# Quad_ESC.net
KiCad netlist of a schematic drawn in EAGLE
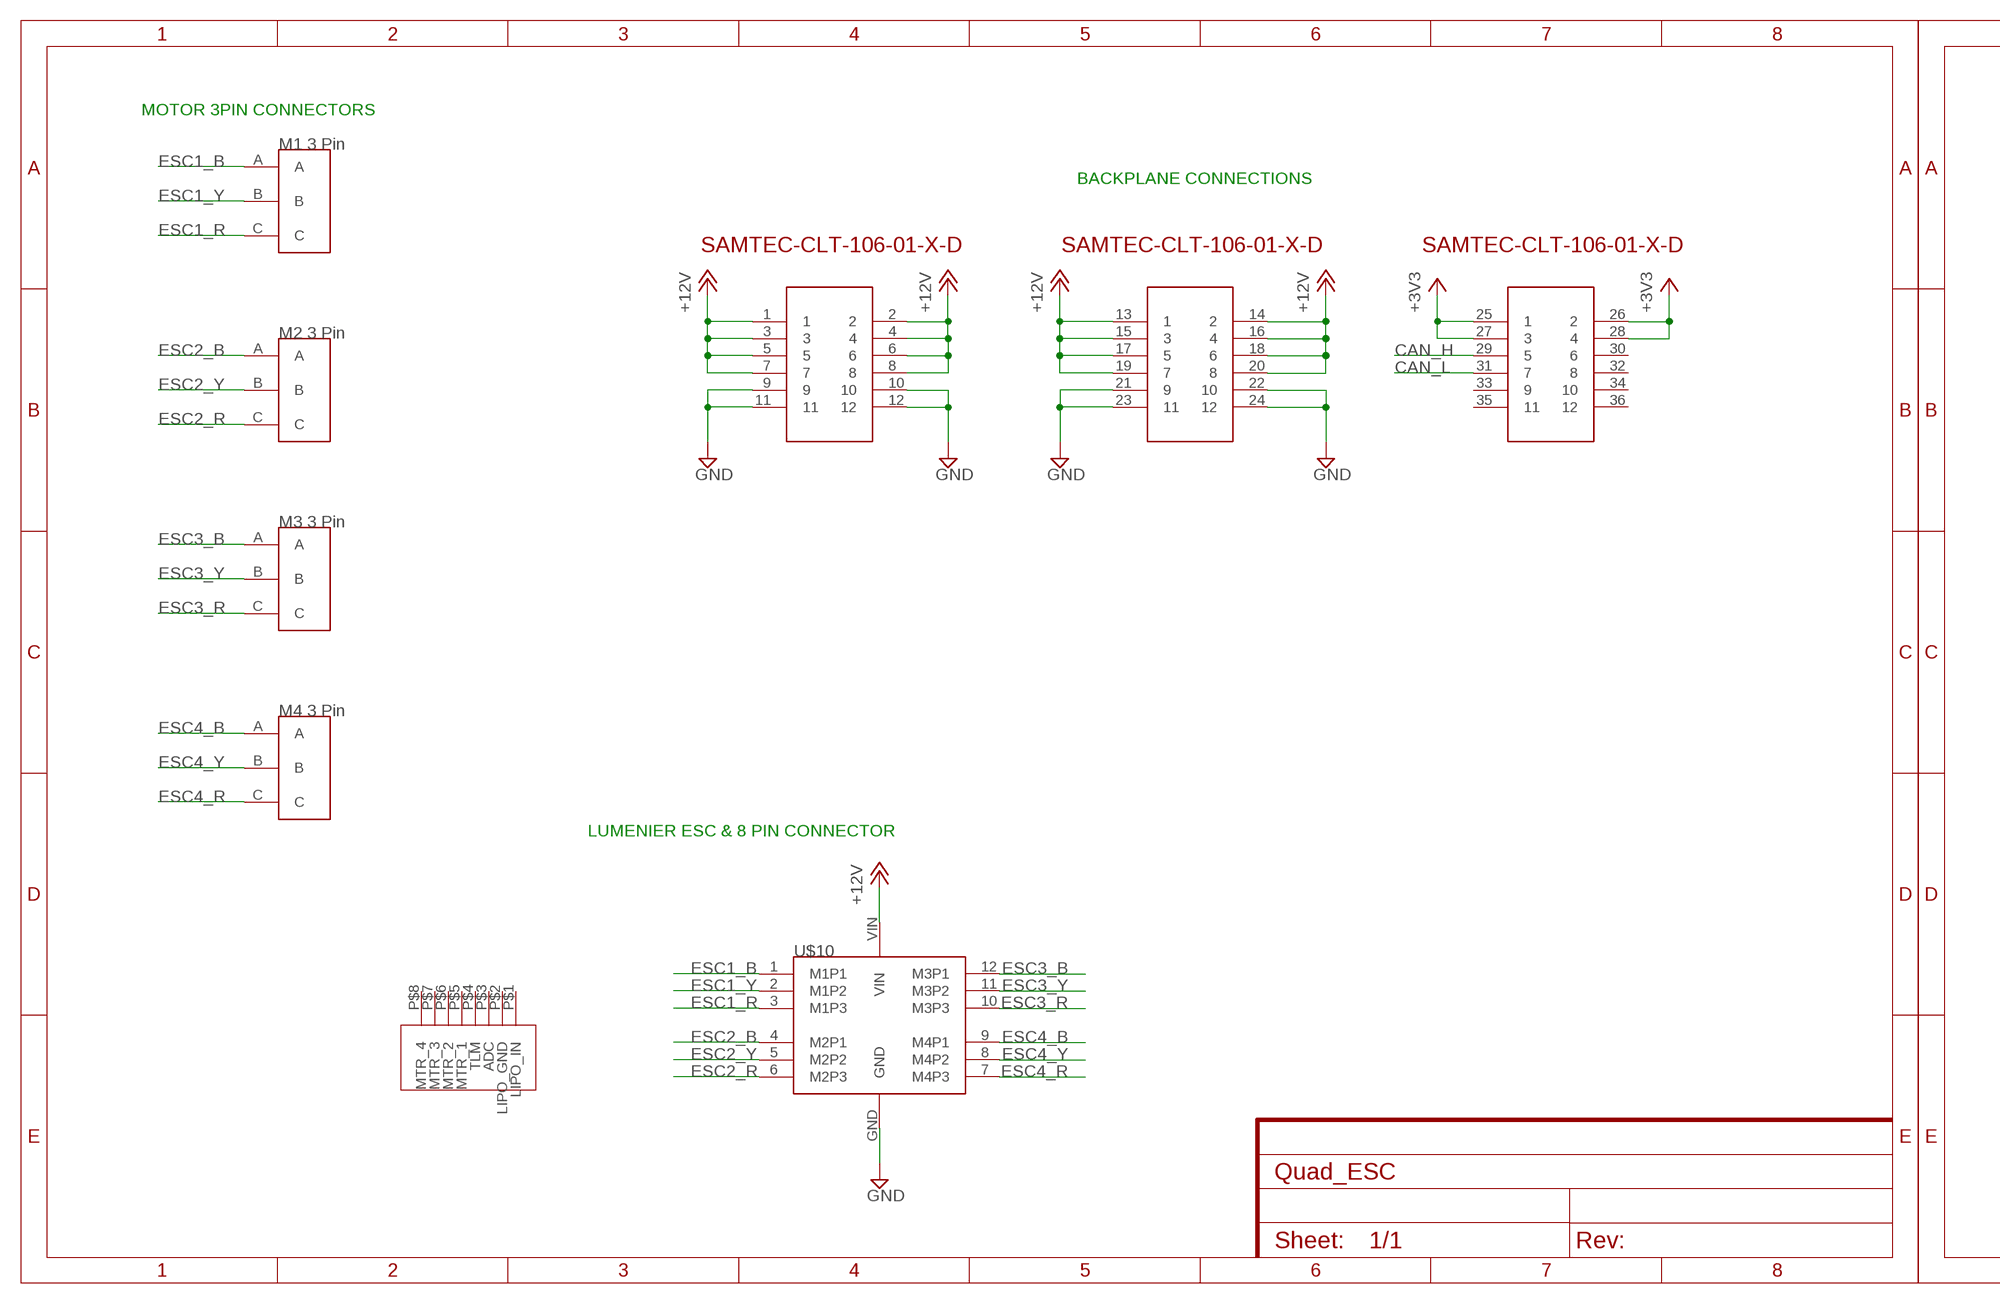
[diagram p0: schematic, sheet 1, part 1 of 2]
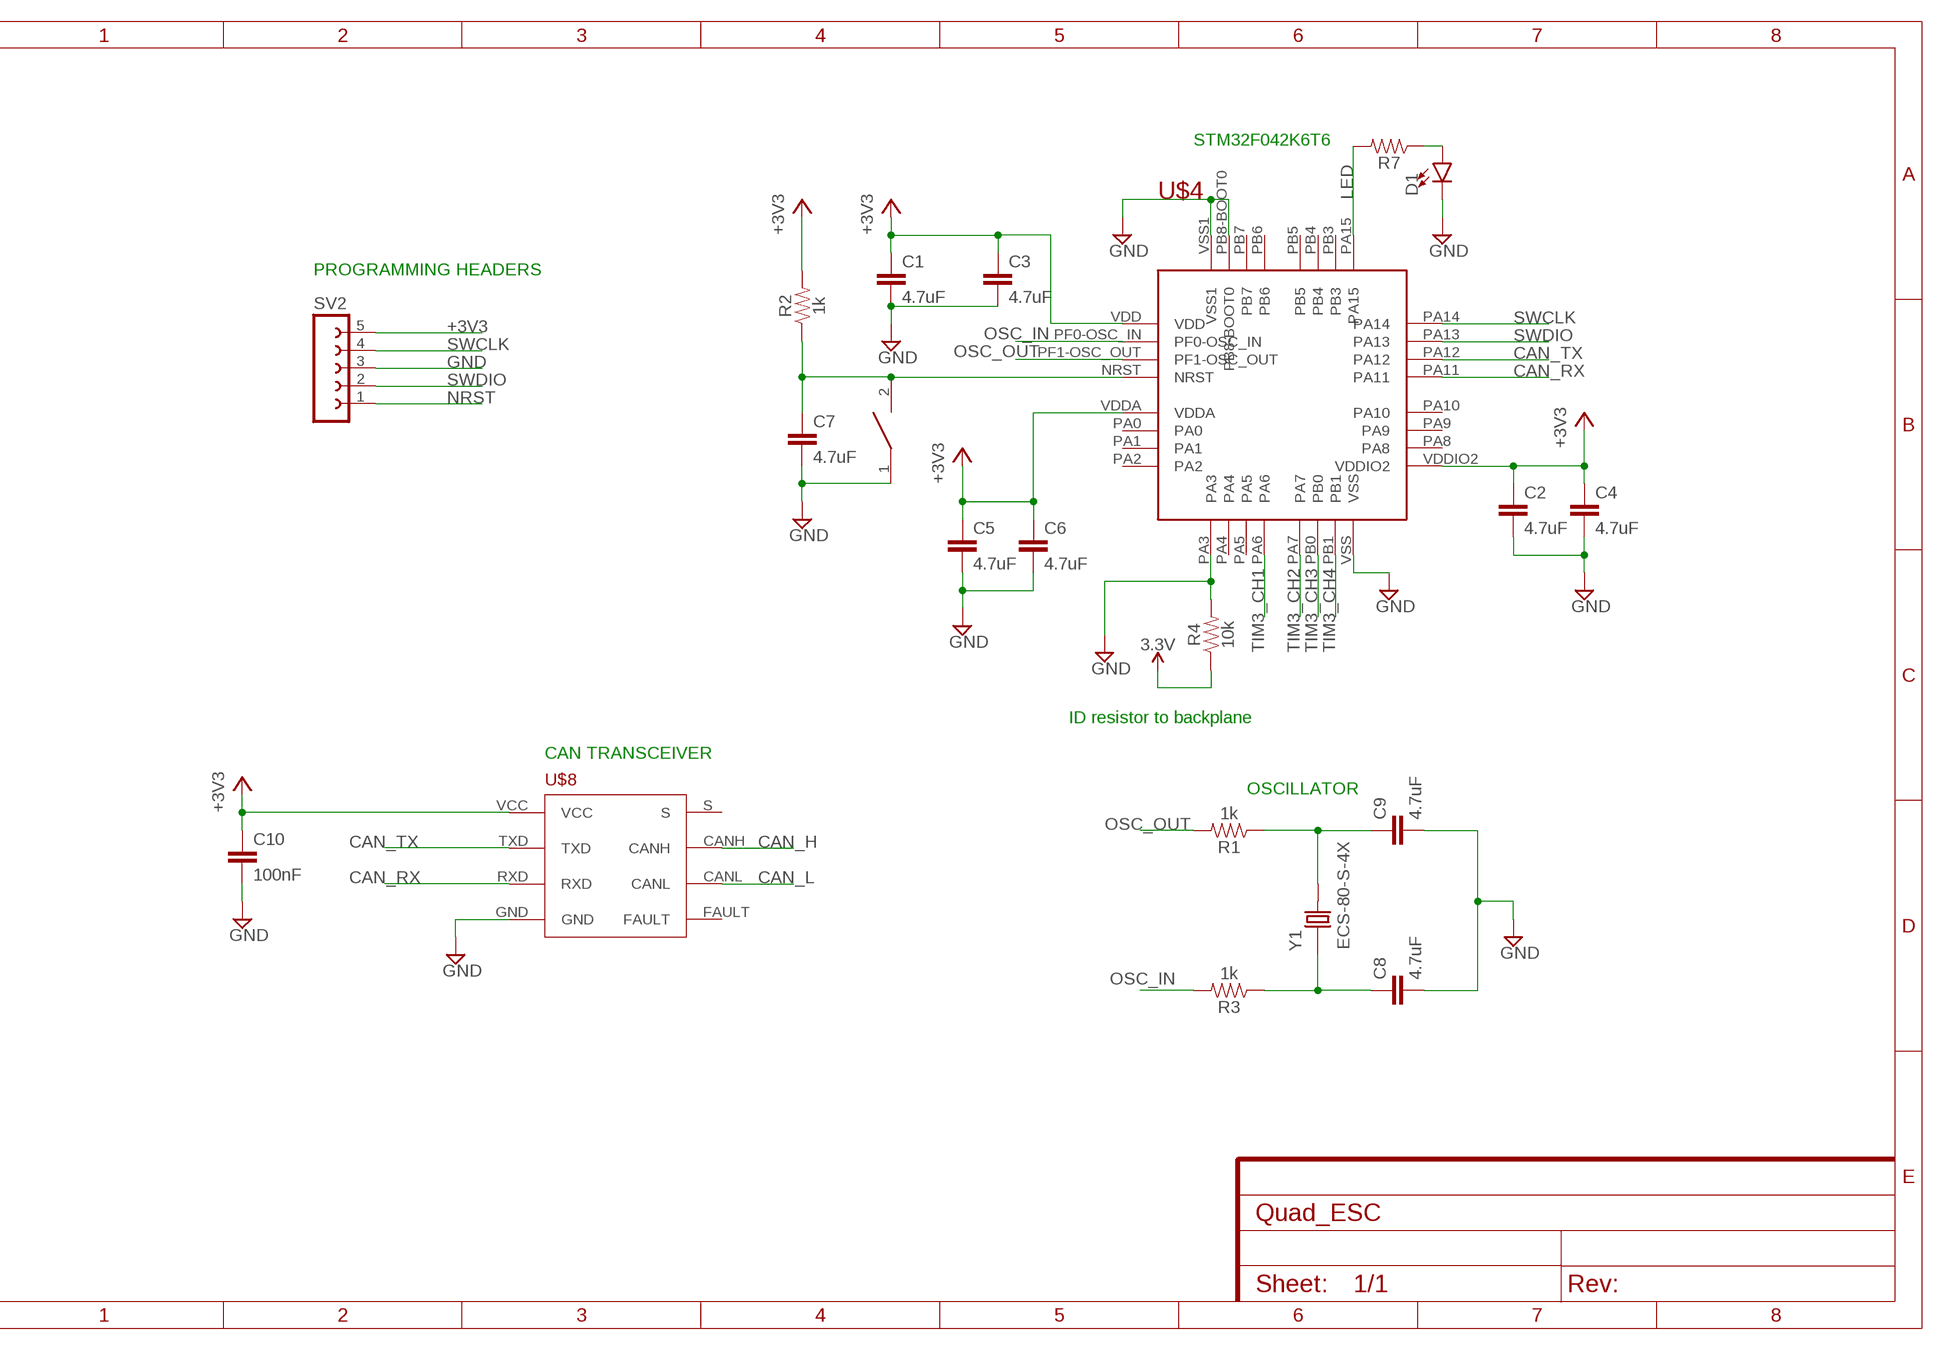
[diagram p1: schematic, sheet 1, part 2 of 2]

(export (version "E")
  (design (tool "Eeschema 10.0.6"))
  (components
    (comp (ref "C1")
      (value "4.7uF")
      (footprint "eagle-import:0603")
      (libsource (lib "eagle-import") (part "4.7UF0603"))
    )
    (comp (ref "C2")
      (value "4.7uF")
      (footprint "eagle-import:0603")
      (libsource (lib "eagle-import") (part "4.7UF0603"))
    )
    (comp (ref "C3")
      (value "4.7uF")
      (footprint "eagle-import:0603")
      (libsource (lib "eagle-import") (part "4.7UF0603"))
    )
    (comp (ref "C4")
      (value "4.7uF")
      (footprint "eagle-import:0603")
      (libsource (lib "eagle-import") (part "4.7UF0603"))
    )
    (comp (ref "C5")
      (value "4.7uF")
      (footprint "eagle-import:0603")
      (libsource (lib "eagle-import") (part "4.7UF0603"))
    )
    (comp (ref "C6")
      (value "4.7uF")
      (footprint "eagle-import:0603")
      (libsource (lib "eagle-import") (part "4.7UF0603"))
    )
    (comp (ref "C7")
      (value "4.7uF")
      (footprint "eagle-import:0603")
      (libsource (lib "eagle-import") (part "4.7UF0603"))
    )
    (comp (ref "C8")
      (value "4.7uF")
      (footprint "eagle-import:0603")
      (libsource (lib "eagle-import") (part "4.7UF0603"))
    )
    (comp (ref "C9")
      (value "4.7uF")
      (footprint "eagle-import:0603")
      (libsource (lib "eagle-import") (part "4.7UF0603"))
    )
    (comp (ref "C10")
      (value "100nF")
      (footprint "eagle-import:0603")
      (libsource (lib "eagle-import") (part "4.7UF0603"))
    )
    (comp (ref "D1")
      (value "LED0603")
      (footprint "eagle-import:LED-0603")
      (libsource (lib "eagle-import") (part "LED0603"))
    )
    (comp (ref "R1")
      (value "1k")
      (footprint "eagle-import:0603")
      (libsource (lib "eagle-import") (part "1KOHM-0603-1/10W-1%"))
    )
    (comp (ref "R2")
      (value "1k")
      (footprint "eagle-import:0603")
      (libsource (lib "eagle-import") (part "1KOHM-0603-1/10W-1%"))
    )
    (comp (ref "R3")
      (value "1k")
      (footprint "eagle-import:0603")
      (libsource (lib "eagle-import") (part "1KOHM-0603-1/10W-1%"))
    )
    (comp (ref "R4")
      (value "10k")
      (footprint "eagle-import:0603")
      (libsource (lib "eagle-import") (part "10KOHM-0603-1/10W-1%"))
    )
    (comp (ref "R7")
      (value "RESISTOR0603")
      (footprint "eagle-import:0603")
      (libsource (lib "eagle-import") (part "RESISTOR0603"))
    )
    (comp (ref "RESET")
      (value "SWITCH")
      (footprint "eagle-import:SW_2512")
      (libsource (lib "eagle-import") (part "SWITCH"))
    )
    (comp (ref "SV2")
      (value "FE05-1")
      (footprint "eagle-import:FE05-1")
      (libsource (lib "eagle-import") (part "FE05-1"))
    )
    (comp (ref "U$1")
      (value "3PINCONNECTOR")
      (footprint "eagle-import:3PINCONNECTOR")
      (libsource (lib "eagle-import") (part "3PINCONNECTOR"))
    )
    (comp (ref "U$2")
      (value "8PIN_CONNECTOR")
      (footprint "eagle-import:8PI_CONNECTOR")
      (libsource (lib "eagle-import") (part "8PIN_CONNECTOR"))
    )
    (comp (ref "U$3")
      (value "BACKPLANE_CONNECTORS")
      (footprint "eagle-import:BACKPLANE_CONNECTORS")
      (libsource (lib "eagle-import") (part "BACKPLANE_CONNECTORS"))
    )
    (comp (ref "U$4")
      (value "STM32F042K6T6")
      (footprint "eagle-import:STM32F042K6T6")
      (libsource (lib "eagle-import") (part "STM32F042K6T6"))
    )
    (comp (ref "U$5")
      (value "3PINCONNECTOR")
      (footprint "eagle-import:3PINCONNECTOR")
      (libsource (lib "eagle-import") (part "3PINCONNECTOR"))
    )
    (comp (ref "U$6")
      (value "3PINCONNECTOR")
      (footprint "eagle-import:3PINCONNECTOR")
      (libsource (lib "eagle-import") (part "3PINCONNECTOR"))
    )
    (comp (ref "U$7")
      (value "3PINCONNECTOR")
      (footprint "eagle-import:3PINCONNECTOR")
      (libsource (lib "eagle-import") (part "3PINCONNECTOR"))
    )
    (comp (ref "U$8")
      (value "TCAN337D")
      (footprint "eagle-import:TCAN337D")
      (libsource (lib "eagle-import") (part "TCAN337D"))
    )
    (comp (ref "U$10")
      (value "LUMENIER_QUAD")
      (footprint "eagle-import:LUMENIER_QUAD")
      (libsource (lib "eagle-import") (part "LUMENIER_QUAD"))
    )
    (comp (ref "Y1")
      (value "ECS-80-S-4X")
      (footprint "eagle-import:XTAL_ECS-80-S-4X")
      (fields (field (name "DIGI-KEY_PART_NUMBER") "X1057-ND") (field (name "MF") "ECS International"))
      (libsource (lib "eagle-import") (part "ECS-80-S-4X"))
    )
  )
  (nets
    (net (code "1") (name "+3V3") (class "Default")
      (node (ref "C1") (pin "1") (pinfunction "1_1") (pintype "passive"))
      (node (ref "C10") (pin "1") (pinfunction "1_1") (pintype "passive"))
      (node (ref "C2") (pin "1") (pinfunction "1_1") (pintype "passive"))
      (node (ref "C3") (pin "1") (pinfunction "1_1") (pintype "passive"))
      (node (ref "C4") (pin "1") (pinfunction "1_1") (pintype "passive"))
      (node (ref "C5") (pin "1") (pinfunction "1_1") (pintype "passive"))
      (node (ref "C6") (pin "1") (pinfunction "1_1") (pintype "passive"))
      (node (ref "R2") (pin "2") (pinfunction "2_2") (pintype "passive"))
      (node (ref "SV2") (pin "5") (pinfunction "5_5") (pintype "passive"))
      (node (ref "U$3") (pin "25") (pinfunction "1_25") (pintype "passive"))
      (node (ref "U$3") (pin "26") (pinfunction "2_26") (pintype "passive"))
      (node (ref "U$3") (pin "27") (pinfunction "3_27") (pintype "passive"))
      (node (ref "U$3") (pin "28") (pinfunction "4_28") (pintype "passive"))
      (node (ref "U$4") (pin "VDD") (pinfunction "VDD_VDD") (pintype "bidirectional"))
      (node (ref "U$4") (pin "VDDA") (pinfunction "VDDA_VDDA") (pintype "bidirectional"))
      (node (ref "U$4") (pin "VDDIO2") (pinfunction "VDDIO2_VDDIO2") (pintype "bidirectional"))
      (node (ref "U$8") (pin "VCC") (pinfunction "VCC_VCC") (pintype "bidirectional"))
    )
    (net (code "2") (name "+12V") (class "Default")
      (node (ref "U$10") (pin "VIN") (pinfunction "VIN_VIN") (pintype "bidirectional"))
      (node (ref "U$3") (pin "1") (pinfunction "1_1") (pintype "passive"))
      (node (ref "U$3") (pin "13") (pinfunction "1_13") (pintype "passive"))
      (node (ref "U$3") (pin "14") (pinfunction "2_14") (pintype "passive"))
      (node (ref "U$3") (pin "15") (pinfunction "3_15") (pintype "passive"))
      (node (ref "U$3") (pin "16") (pinfunction "4_16") (pintype "passive"))
      (node (ref "U$3") (pin "17") (pinfunction "5_17") (pintype "passive"))
      (node (ref "U$3") (pin "18") (pinfunction "6_18") (pintype "passive"))
      (node (ref "U$3") (pin "19") (pinfunction "7_19") (pintype "passive"))
      (node (ref "U$3") (pin "2") (pinfunction "2_2") (pintype "passive"))
      (node (ref "U$3") (pin "20") (pinfunction "8_20") (pintype "passive"))
      (node (ref "U$3") (pin "3") (pinfunction "3_3") (pintype "passive"))
      (node (ref "U$3") (pin "4") (pinfunction "4_4") (pintype "passive"))
      (node (ref "U$3") (pin "5") (pinfunction "5_5") (pintype "passive"))
      (node (ref "U$3") (pin "6") (pinfunction "6_6") (pintype "passive"))
      (node (ref "U$3") (pin "7") (pinfunction "7_7") (pintype "passive"))
      (node (ref "U$3") (pin "8") (pinfunction "8_8") (pintype "passive"))
    )
    (net (code "3") (name "/CAN_H") (class "Default")
      (node (ref "U$3") (pin "29") (pinfunction "5_29") (pintype "passive"))
      (node (ref "U$8") (pin "CANH") (pinfunction "CANH_CANH") (pintype "bidirectional"))
    )
    (net (code "4") (name "/CAN_L") (class "Default")
      (node (ref "U$3") (pin "31") (pinfunction "7_31") (pintype "passive"))
      (node (ref "U$8") (pin "CANL") (pinfunction "CANL_CANL") (pintype "bidirectional"))
    )
    (net (code "5") (name "/CAN_RX") (class "Default")
      (node (ref "U$4") (pin "PA11") (pinfunction "PA11_PA11") (pintype "bidirectional"))
      (node (ref "U$8") (pin "RXD") (pinfunction "RXD_RXD") (pintype "bidirectional"))
    )
    (net (code "6") (name "/CAN_TX") (class "Default")
      (node (ref "U$4") (pin "PA12") (pinfunction "PA12_PA12") (pintype "bidirectional"))
      (node (ref "U$8") (pin "TXD") (pinfunction "TXD_TXD") (pintype "bidirectional"))
    )
    (net (code "7") (name "/ESC1_B") (class "Default")
      (node (ref "U$1") (pin "A") (pinfunction "A_A") (pintype "bidirectional"))
      (node (ref "U$10") (pin "1") (pinfunction "M1P1_1") (pintype "bidirectional"))
    )
    (net (code "8") (name "/ESC1_R") (class "Default")
      (node (ref "U$1") (pin "C") (pinfunction "C_C") (pintype "bidirectional"))
      (node (ref "U$10") (pin "3") (pinfunction "M1P3_3") (pintype "bidirectional"))
    )
    (net (code "9") (name "/ESC1_Y") (class "Default")
      (node (ref "U$1") (pin "B") (pinfunction "B_B") (pintype "bidirectional"))
      (node (ref "U$10") (pin "2") (pinfunction "M1P2_2") (pintype "bidirectional"))
    )
    (net (code "10") (name "/ESC2_B") (class "Default")
      (node (ref "U$10") (pin "4") (pinfunction "M2P1_4") (pintype "bidirectional"))
      (node (ref "U$5") (pin "A") (pinfunction "A_A") (pintype "bidirectional"))
    )
    (net (code "11") (name "/ESC2_R") (class "Default")
      (node (ref "U$10") (pin "6") (pinfunction "M2P3_6") (pintype "bidirectional"))
      (node (ref "U$5") (pin "C") (pinfunction "C_C") (pintype "bidirectional"))
    )
    (net (code "12") (name "/ESC2_Y") (class "Default")
      (node (ref "U$10") (pin "5") (pinfunction "M2P2_5") (pintype "bidirectional"))
      (node (ref "U$5") (pin "B") (pinfunction "B_B") (pintype "bidirectional"))
    )
    (net (code "13") (name "/ESC3_B") (class "Default")
      (node (ref "U$10") (pin "12") (pinfunction "M3P1_12") (pintype "bidirectional"))
      (node (ref "U$6") (pin "A") (pinfunction "A_A") (pintype "bidirectional"))
    )
    (net (code "14") (name "/ESC3_R") (class "Default")
      (node (ref "U$10") (pin "10") (pinfunction "M3P3_10") (pintype "bidirectional"))
      (node (ref "U$6") (pin "C") (pinfunction "C_C") (pintype "bidirectional"))
    )
    (net (code "15") (name "/ESC3_Y") (class "Default")
      (node (ref "U$10") (pin "11") (pinfunction "M3P2_11") (pintype "bidirectional"))
      (node (ref "U$6") (pin "B") (pinfunction "B_B") (pintype "bidirectional"))
    )
    (net (code "16") (name "/ESC4_B") (class "Default")
      (node (ref "U$10") (pin "9") (pinfunction "M4P1_9") (pintype "bidirectional"))
      (node (ref "U$7") (pin "A") (pinfunction "A_A") (pintype "bidirectional"))
    )
    (net (code "17") (name "/ESC4_R") (class "Default")
      (node (ref "U$10") (pin "7") (pinfunction "M4P3_7") (pintype "bidirectional"))
      (node (ref "U$7") (pin "C") (pinfunction "C_C") (pintype "bidirectional"))
    )
    (net (code "18") (name "/ESC4_Y") (class "Default")
      (node (ref "U$10") (pin "8") (pinfunction "M4P2_8") (pintype "bidirectional"))
      (node (ref "U$7") (pin "B") (pinfunction "B_B") (pintype "bidirectional"))
    )
    (net (code "19") (name "/LED") (class "Default")
      (node (ref "R7") (pin "2") (pinfunction "2_2") (pintype "passive"))
      (node (ref "U$4") (pin "PA15") (pinfunction "PA15_PA15") (pintype "bidirectional"))
    )
    (net (code "20") (name "/NRST") (class "Default")
      (node (ref "SV2") (pin "1") (pinfunction "1_1") (pintype "passive"))
    )
    (net (code "21") (name "/OSC_IN") (class "Default")
      (node (ref "R3") (pin "2") (pinfunction "2_2") (pintype "passive"))
      (node (ref "U$4") (pin "PF0-OSC_IN") (pinfunction "PF0-OSC_IN_PF0-OSC_IN") (pintype "bidirectional"))
    )
    (net (code "22") (name "/OSC_OUT") (class "Default")
      (node (ref "R1") (pin "2") (pinfunction "2_2") (pintype "passive"))
      (node (ref "U$4") (pin "PF1-OSC_OUT") (pinfunction "PF1-OSC_OUT_PF1-OSC_OUT") (pintype "bidirectional"))
    )
    (net (code "23") (name "/SWCLK") (class "Default")
      (node (ref "SV2") (pin "4") (pinfunction "4_4") (pintype "passive"))
      (node (ref "U$4") (pin "PA14") (pinfunction "PA14_PA14") (pintype "bidirectional"))
    )
    (net (code "24") (name "/SWDIO") (class "Default")
      (node (ref "SV2") (pin "2") (pinfunction "2_2") (pintype "passive"))
      (node (ref "U$4") (pin "PA13") (pinfunction "PA13_PA13") (pintype "bidirectional"))
    )
    (net (code "25") (name "/TIM3_CH1") (class "Default")
      (node (ref "U$4") (pin "PA6") (pinfunction "PA6_PA6") (pintype "bidirectional"))
    )
    (net (code "26") (name "/TIM3_CH2") (class "Default")
      (node (ref "U$4") (pin "PA7") (pinfunction "PA7_PA7") (pintype "bidirectional"))
    )
    (net (code "27") (name "/TIM3_CH3") (class "Default")
      (node (ref "U$4") (pin "PB0") (pinfunction "PB0_PB0") (pintype "bidirectional"))
    )
    (net (code "28") (name "/TIM3_CH4") (class "Default")
      (node (ref "U$4") (pin "PB1") (pinfunction "PB1_PB1") (pintype "bidirectional"))
    )
    (net (code "29") (name "3.3V") (class "Default")
      (node (ref "R4") (pin "1") (pinfunction "1_1") (pintype "passive"))
    )
    (net (code "30") (name "GND") (class "Default")
      (node (ref "C1") (pin "2") (pinfunction "2_2") (pintype "passive"))
      (node (ref "C10") (pin "2") (pinfunction "2_2") (pintype "passive"))
      (node (ref "C2") (pin "2") (pinfunction "2_2") (pintype "passive"))
      (node (ref "C3") (pin "2") (pinfunction "2_2") (pintype "passive"))
      (node (ref "C4") (pin "2") (pinfunction "2_2") (pintype "passive"))
      (node (ref "C5") (pin "2") (pinfunction "2_2") (pintype "passive"))
      (node (ref "C6") (pin "2") (pinfunction "2_2") (pintype "passive"))
      (node (ref "C7") (pin "2") (pinfunction "2_2") (pintype "passive"))
      (node (ref "C8") (pin "2") (pinfunction "2_2") (pintype "passive"))
      (node (ref "C9") (pin "2") (pinfunction "2_2") (pintype "passive"))
      (node (ref "D1") (pin "C") (pinfunction "C_C") (pintype "passive"))
      (node (ref "R4") (pin "2") (pinfunction "2_2") (pintype "passive"))
      (node (ref "RESET") (pin "1") (pinfunction "P$1_1") (pintype "bidirectional"))
      (node (ref "SV2") (pin "3") (pinfunction "3_3") (pintype "passive"))
      (node (ref "U$10") (pin "GND") (pinfunction "GND_GND") (pintype "bidirectional"))
      (node (ref "U$3") (pin "10") (pinfunction "10_10") (pintype "passive"))
      (node (ref "U$3") (pin "11") (pinfunction "11_11") (pintype "passive"))
      (node (ref "U$3") (pin "12") (pinfunction "12_12") (pintype "passive"))
      (node (ref "U$3") (pin "21") (pinfunction "9_21") (pintype "passive"))
      (node (ref "U$3") (pin "22") (pinfunction "10_22") (pintype "passive"))
      (node (ref "U$3") (pin "23") (pinfunction "11_23") (pintype "passive"))
      (node (ref "U$3") (pin "24") (pinfunction "12_24") (pintype "passive"))
      (node (ref "U$3") (pin "9") (pinfunction "9_9") (pintype "passive"))
      (node (ref "U$4") (pin "PA3") (pinfunction "PA3_PA3") (pintype "bidirectional"))
      (node (ref "U$4") (pin "PB8-BOOT0") (pinfunction "PB8-BOOT0_PB8-BOOT0") (pintype "bidirectional"))
      (node (ref "U$4") (pin "VSS") (pinfunction "VSS_VSS") (pintype "bidirectional"))
      (node (ref "U$4") (pin "VSS1") (pinfunction "VSS1_VSS1") (pintype "bidirectional"))
      (node (ref "U$8") (pin "GND") (pinfunction "GND_GND") (pintype "bidirectional"))
    )
    (net (code "31") (name "Net-(C8-Pad1)") (class "Default")
      (node (ref "C8") (pin "1") (pinfunction "1_1") (pintype "passive"))
      (node (ref "R3") (pin "1") (pinfunction "1_1") (pintype "passive"))
      (node (ref "Y1") (pin "1") (pinfunction "1_1") (pintype "passive"))
    )
    (net (code "32") (name "Net-(C9-Pad1)") (class "Default")
      (node (ref "C9") (pin "1") (pinfunction "1_1") (pintype "passive"))
      (node (ref "R1") (pin "1") (pinfunction "1_1") (pintype "passive"))
      (node (ref "Y1") (pin "2") (pinfunction "2_2") (pintype "passive"))
    )
    (net (code "33") (name "Net-(D1-PadA)") (class "Default")
      (node (ref "D1") (pin "A") (pinfunction "A_A") (pintype "passive"))
      (node (ref "R7") (pin "1") (pinfunction "1_1") (pintype "passive"))
    )
    (net (code "34") (name "Net-(RESET-P$2)") (class "Default")
      (node (ref "C7") (pin "1") (pinfunction "1_1") (pintype "passive"))
      (node (ref "R2") (pin "1") (pinfunction "1_1") (pintype "passive"))
      (node (ref "RESET") (pin "2") (pinfunction "P$2_2") (pintype "bidirectional"))
      (node (ref "U$4") (pin "NRST") (pinfunction "NRST_NRST") (pintype "bidirectional"))
    )
    (net (code "35") (name "unconnected-(U$2-ADC-PadP$3)") (class "Default")
      (node (ref "U$2") (pin "P$3") (pinfunction "ADC_P$3") (pintype "bidirectional"))
    )
    (net (code "36") (name "unconnected-(U$2-LIPO_GND-PadP$2)") (class "Default")
      (node (ref "U$2") (pin "P$2") (pinfunction "LIPO_GND_P$2") (pintype "bidirectional"))
    )
    (net (code "37") (name "unconnected-(U$2-LIPO_IN-PadP$1)") (class "Default")
      (node (ref "U$2") (pin "P$1") (pinfunction "LIPO_IN_P$1") (pintype "bidirectional"))
    )
    (net (code "38") (name "unconnected-(U$2-MTR_1-PadP$5)") (class "Default")
      (node (ref "U$2") (pin "P$5") (pinfunction "MTR_1_P$5") (pintype "bidirectional"))
    )
    (net (code "39") (name "unconnected-(U$2-MTR_2-PadP$6)") (class "Default")
      (node (ref "U$2") (pin "P$6") (pinfunction "MTR_2_P$6") (pintype "bidirectional"))
    )
    (net (code "40") (name "unconnected-(U$2-MTR_3-PadP$7)") (class "Default")
      (node (ref "U$2") (pin "P$7") (pinfunction "MTR_3_P$7") (pintype "bidirectional"))
    )
    (net (code "41") (name "unconnected-(U$2-MTR_4-PadP$8)") (class "Default")
      (node (ref "U$2") (pin "P$8") (pinfunction "MTR_4_P$8") (pintype "bidirectional"))
    )
    (net (code "42") (name "unconnected-(U$2-TLM-PadP$4)") (class "Default")
      (node (ref "U$2") (pin "P$4") (pinfunction "TLM_P$4") (pintype "bidirectional"))
    )
    (net (code "43") (name "unconnected-(U$3C-6-Pad30)") (class "Default")
      (node (ref "U$3") (pin "30") (pinfunction "6_30") (pintype "passive"))
    )
    (net (code "44") (name "unconnected-(U$3C-8-Pad32)") (class "Default")
      (node (ref "U$3") (pin "32") (pinfunction "8_32") (pintype "passive"))
    )
    (net (code "45") (name "unconnected-(U$3C-9-Pad33)") (class "Default")
      (node (ref "U$3") (pin "33") (pinfunction "9_33") (pintype "passive"))
    )
    (net (code "46") (name "unconnected-(U$3C-10-Pad34)") (class "Default")
      (node (ref "U$3") (pin "34") (pinfunction "10_34") (pintype "passive"))
    )
    (net (code "47") (name "unconnected-(U$3C-11-Pad35)") (class "Default")
      (node (ref "U$3") (pin "35") (pinfunction "11_35") (pintype "passive"))
    )
    (net (code "48") (name "unconnected-(U$3C-12-Pad36)") (class "Default")
      (node (ref "U$3") (pin "36") (pinfunction "12_36") (pintype "passive"))
    )
    (net (code "49") (name "unconnected-(U$4-PadPA0)") (class "Default")
      (node (ref "U$4") (pin "PA0") (pinfunction "PA0_PA0") (pintype "bidirectional"))
    )
    (net (code "50") (name "unconnected-(U$4-PadPA1)") (class "Default")
      (node (ref "U$4") (pin "PA1") (pinfunction "PA1_PA1") (pintype "bidirectional"))
    )
    (net (code "51") (name "unconnected-(U$4-PadPA2)") (class "Default")
      (node (ref "U$4") (pin "PA2") (pinfunction "PA2_PA2") (pintype "bidirectional"))
    )
    (net (code "52") (name "unconnected-(U$4-PadPA4)") (class "Default")
      (node (ref "U$4") (pin "PA4") (pinfunction "PA4_PA4") (pintype "bidirectional"))
    )
    (net (code "53") (name "unconnected-(U$4-PadPA5)") (class "Default")
      (node (ref "U$4") (pin "PA5") (pinfunction "PA5_PA5") (pintype "bidirectional"))
    )
    (net (code "54") (name "unconnected-(U$4-PadPA8)") (class "Default")
      (node (ref "U$4") (pin "PA8") (pinfunction "PA8_PA8") (pintype "bidirectional"))
    )
    (net (code "55") (name "unconnected-(U$4-PadPA9)") (class "Default")
      (node (ref "U$4") (pin "PA9") (pinfunction "PA9_PA9") (pintype "bidirectional"))
    )
    (net (code "56") (name "unconnected-(U$4-PadPA10)") (class "Default")
      (node (ref "U$4") (pin "PA10") (pinfunction "PA10_PA10") (pintype "bidirectional"))
    )
    (net (code "57") (name "unconnected-(U$4-PadPB3)") (class "Default")
      (node (ref "U$4") (pin "PB3") (pinfunction "PB3_PB3") (pintype "bidirectional"))
    )
    (net (code "58") (name "unconnected-(U$4-PadPB4)") (class "Default")
      (node (ref "U$4") (pin "PB4") (pinfunction "PB4_PB4") (pintype "bidirectional"))
    )
    (net (code "59") (name "unconnected-(U$4-PadPB5)") (class "Default")
      (node (ref "U$4") (pin "PB5") (pinfunction "PB5_PB5") (pintype "bidirectional"))
    )
    (net (code "60") (name "unconnected-(U$4-PadPB6)") (class "Default")
      (node (ref "U$4") (pin "PB6") (pinfunction "PB6_PB6") (pintype "bidirectional"))
    )
    (net (code "61") (name "unconnected-(U$4-PadPB7)") (class "Default")
      (node (ref "U$4") (pin "PB7") (pinfunction "PB7_PB7") (pintype "bidirectional"))
    )
    (net (code "62") (name "unconnected-(U$8-PadFAULT)") (class "Default")
      (node (ref "U$8") (pin "FAULT") (pinfunction "FAULT_FAULT") (pintype "bidirectional"))
    )
    (net (code "63") (name "unconnected-(U$8-PadS)") (class "Default")
      (node (ref "U$8") (pin "S") (pinfunction "S_S") (pintype "bidirectional"))
    )
  )
)
